# InputFilter.net
KiCad netlist of a schematic drawn in Altium Designer
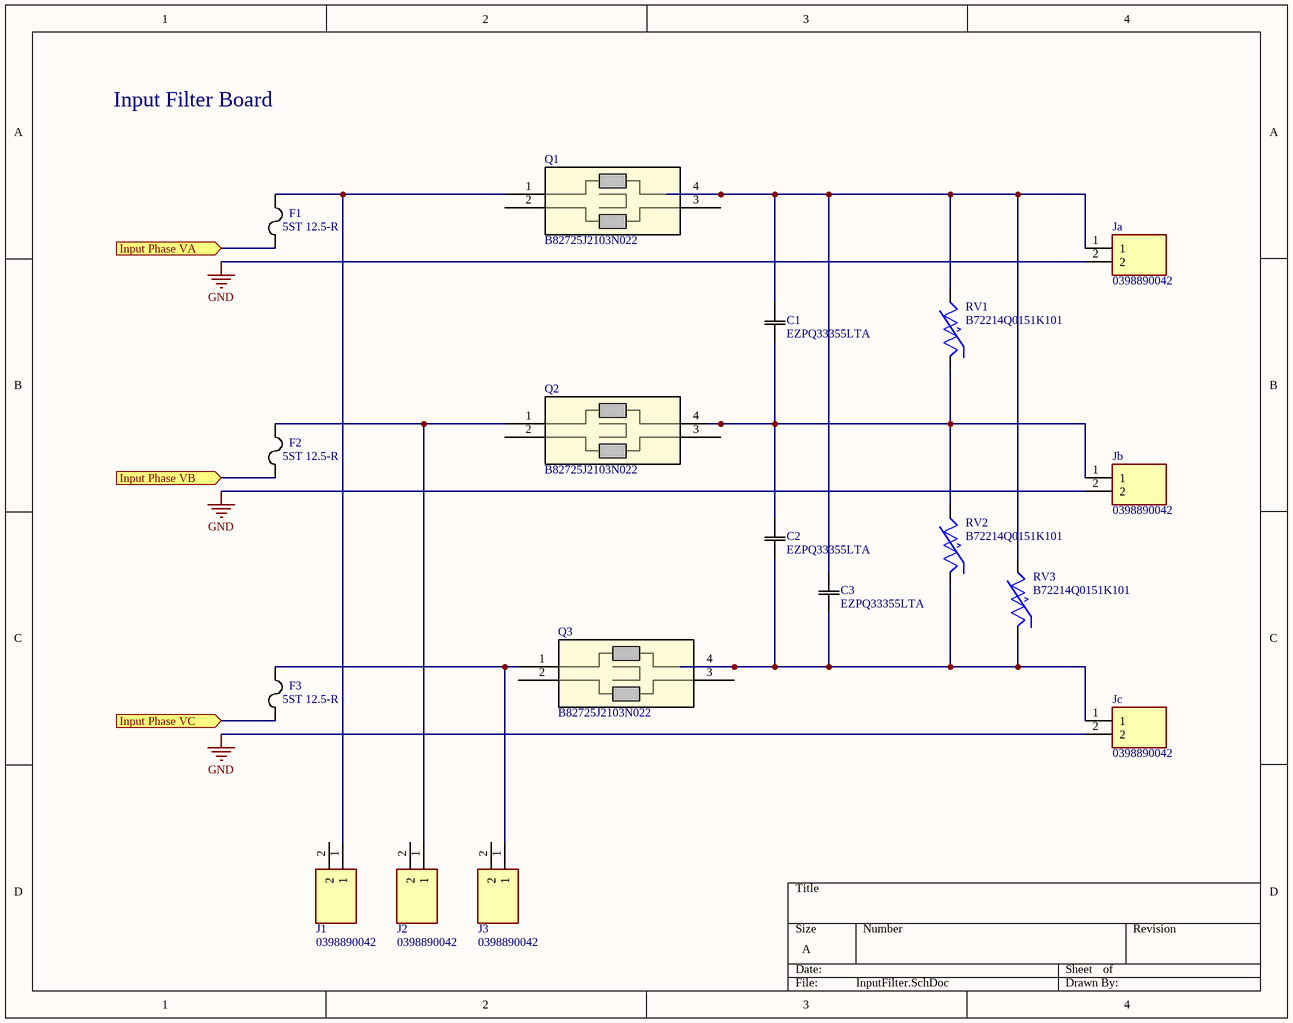
[diagram p0: InputFilter.SchDoc]

(export (version "E")
  (design (tool "Eeschema 10.0.6"))
  (components
    (comp (ref "C1")
      (value "EZPQ33355LTA")
      (footprint "CAP_EZPQ33_41p5X17-37p5_PAN")
      (description "No Description Available")
      (libsource (lib "EZPQ33355LTA") (part "EZPQ33355LTA"))
    )
    (comp (ref "C2")
      (value "EZPQ33355LTA")
      (footprint "CAP_EZPQ33_41p5X17-37p5_PAN")
      (description "No Description Available")
      (libsource (lib "EZPQ33355LTA") (part "EZPQ33355LTA"))
    )
    (comp (ref "C3")
      (value "EZPQ33355LTA")
      (footprint "CAP_EZPQ33_41p5X17-37p5_PAN")
      (description "No Description Available")
      (libsource (lib "EZPQ33355LTA") (part "EZPQ33355LTA"))
    )
    (comp (ref "F1")
      (value "5ST 12.5-R")
      (footprint "5S_MELF_BEL")
      (description "No Description Available")
      (libsource (lib "5ST12P5-R") (part "5ST 12.5-R"))
    )
    (comp (ref "F2")
      (value "5ST 12.5-R")
      (footprint "5S_MELF_BEL")
      (description "No Description Available")
      (libsource (lib "5ST12P5-R") (part "5ST 12.5-R"))
    )
    (comp (ref "F3")
      (value "5ST 12.5-R")
      (footprint "5S_MELF_BEL")
      (description "No Description Available")
      (libsource (lib "5ST12P5-R") (part "5ST 12.5-R"))
    )
    (comp (ref "J1")
      (value "0398890042")
      (footprint "0398890042")
      (description "Conn Eurostyle Block 2 POS 5.08mm Solder ST Thru-Hole 17.5A/Contact")
      (libsource (lib "") (part "0398890042_1"))
    )
    (comp (ref "J2")
      (value "0398890042")
      (footprint "0398890042")
      (description "Conn Eurostyle Block 2 POS 5.08mm Solder ST Thru-Hole 17.5A/Contact")
      (libsource (lib "") (part "0398890042_1"))
    )
    (comp (ref "J3")
      (value "0398890042")
      (footprint "0398890042")
      (description "Conn Eurostyle Block 2 POS 5.08mm Solder ST Thru-Hole 17.5A/Contact")
      (libsource (lib "") (part "0398890042_1"))
    )
    (comp (ref "Ja")
      (value "0398890042")
      (footprint "0398890042")
      (description "Conn Eurostyle Block 2 POS 5.08mm Solder ST Thru-Hole 17.5A/Contact")
      (libsource (lib "0398890042") (part "0398890042"))
    )
    (comp (ref "Jb")
      (value "0398890042")
      (footprint "0398890042")
      (description "Conn Eurostyle Block 2 POS 5.08mm Solder ST Thru-Hole 17.5A/Contact")
      (libsource (lib "0398890042") (part "0398890042"))
    )
    (comp (ref "Jc")
      (value "0398890042")
      (footprint "0398890042")
      (description "Conn Eurostyle Block 2 POS 5.08mm Solder ST Thru-Hole 17.5A/Contact")
      (libsource (lib "0398890042") (part "0398890042"))
    )
    (comp (ref "Q1")
      (value "B82725J2103N022")
      (footprint "B82725J2103N022_TDK")
      (description "No Description Available")
      (libsource (lib "B82725J2103N022") (part "B82725J2103N022"))
    )
    (comp (ref "Q2")
      (value "B82725J2103N022")
      (footprint "B82725J2103N022_TDK")
      (description "No Description Available")
      (libsource (lib "B82725J2103N022") (part "B82725J2103N022"))
    )
    (comp (ref "Q3")
      (value "B82725J2103N022")
      (footprint "B82725J2103N022_TDK")
      (description "No Description Available")
      (libsource (lib "B82725J2103N022") (part "B82725J2103N022"))
    )
    (comp (ref "RV1")
      (value "B72214Q0151K101")
      (footprint "VAR_B72214Q0151K101")
      (description "240 V 8 kA Varistor 1 Circuit Through Hole Radial")
      (fields (field (name "MF") "EPCOS"))
      (libsource (lib "B72214Q0151K101") (part "B72214Q0151K101"))
    )
    (comp (ref "RV2")
      (value "B72214Q0151K101")
      (footprint "VAR_B72214Q0151K101")
      (description "240 V 8 kA Varistor 1 Circuit Through Hole Radial")
      (fields (field (name "MF") "EPCOS"))
      (libsource (lib "B72214Q0151K101") (part "B72214Q0151K101"))
    )
    (comp (ref "RV3")
      (value "B72214Q0151K101")
      (footprint "VAR_B72214Q0151K101")
      (description "240 V 8 kA Varistor 1 Circuit Through Hole Radial")
      (fields (field (name "MF") "EPCOS"))
      (libsource (lib "B72214Q0151K101") (part "B72214Q0151K101"))
    )
  )
  (nets
    (net (code "1") (name "/Input Phase VA") (class "Default")
      (node (ref "F1") (pin "1") (pinfunction "1_1") (pintype "passive"))
    )
    (net (code "2") (name "/Input Phase VB") (class "Default")
      (node (ref "F2") (pin "1") (pinfunction "1_1") (pintype "passive"))
    )
    (net (code "3") (name "/Input Phase VC") (class "Default")
      (node (ref "F3") (pin "1") (pinfunction "1_1") (pintype "passive"))
    )
    (net (code "4") (name "GND") (class "Default")
      (node (ref "Ja") (pin "2") (pinfunction "2_2") (pintype "passive"))
      (node (ref "Jb") (pin "2") (pinfunction "2_2") (pintype "passive"))
      (node (ref "Jc") (pin "2") (pinfunction "2_2") (pintype "passive"))
    )
    (net (code "5") (name "Net-(C1-Pad1)") (class "Default")
      (node (ref "C1") (pin "1") (pinfunction "1_1") (pintype "passive"))
      (node (ref "C2") (pin "2") (pinfunction "2_2") (pintype "passive"))
      (node (ref "Jb") (pin "1") (pinfunction "1_1") (pintype "passive"))
      (node (ref "Q2") (pin "4") (pinfunction "4_4") (pintype "passive"))
      (node (ref "RV1") (pin "1") (pinfunction "1_1") (pintype "passive"))
      (node (ref "RV2") (pin "2") (pinfunction "2_2") (pintype "passive"))
    )
    (net (code "6") (name "Net-(C1-Pad2)") (class "Default")
      (node (ref "C1") (pin "2") (pinfunction "2_2") (pintype "passive"))
      (node (ref "C3") (pin "2") (pinfunction "2_2") (pintype "passive"))
      (node (ref "Ja") (pin "1") (pinfunction "1_1") (pintype "passive"))
      (node (ref "Q1") (pin "4") (pinfunction "4_4") (pintype "passive"))
      (node (ref "RV1") (pin "2") (pinfunction "2_2") (pintype "passive"))
      (node (ref "RV3") (pin "2") (pinfunction "2_2") (pintype "passive"))
    )
    (net (code "7") (name "Net-(C2-Pad1)") (class "Default")
      (node (ref "C2") (pin "1") (pinfunction "1_1") (pintype "passive"))
      (node (ref "C3") (pin "1") (pinfunction "1_1") (pintype "passive"))
      (node (ref "Jc") (pin "1") (pinfunction "1_1") (pintype "passive"))
      (node (ref "Q3") (pin "4") (pinfunction "4_4") (pintype "passive"))
      (node (ref "RV2") (pin "1") (pinfunction "1_1") (pintype "passive"))
      (node (ref "RV3") (pin "1") (pinfunction "1_1") (pintype "passive"))
    )
    (net (code "8") (name "Net-(F1-Pad2)") (class "Default")
      (node (ref "F1") (pin "2") (pinfunction "2_2") (pintype "passive"))
      (node (ref "J1") (pin "1") (pinfunction "1_1") (pintype "passive"))
      (node (ref "Q1") (pin "1") (pinfunction "1_1") (pintype "passive"))
    )
    (net (code "9") (name "Net-(F2-Pad2)") (class "Default")
      (node (ref "F2") (pin "2") (pinfunction "2_2") (pintype "passive"))
      (node (ref "J2") (pin "1") (pinfunction "1_1") (pintype "passive"))
      (node (ref "Q2") (pin "1") (pinfunction "1_1") (pintype "passive"))
    )
    (net (code "10") (name "Net-(F3-Pad2)") (class "Default")
      (node (ref "F3") (pin "2") (pinfunction "2_2") (pintype "passive"))
      (node (ref "J3") (pin "1") (pinfunction "1_1") (pintype "passive"))
      (node (ref "Q3") (pin "1") (pinfunction "1_1") (pintype "passive"))
    )
    (net (code "11") (name "unconnected-(J1-Pad2)") (class "Default")
      (node (ref "J1") (pin "2") (pinfunction "2_2") (pintype "passive"))
    )
    (net (code "12") (name "unconnected-(J2-Pad2)") (class "Default")
      (node (ref "J2") (pin "2") (pinfunction "2_2") (pintype "passive"))
    )
    (net (code "13") (name "unconnected-(J3-Pad2)") (class "Default")
      (node (ref "J3") (pin "2") (pinfunction "2_2") (pintype "passive"))
    )
    (net (code "14") (name "unconnected-(Q1-Pad2)") (class "Default")
      (node (ref "Q1") (pin "2") (pinfunction "2_2") (pintype "passive"))
    )
    (net (code "15") (name "unconnected-(Q1-Pad3)") (class "Default")
      (node (ref "Q1") (pin "3") (pinfunction "3_3") (pintype "passive"))
    )
    (net (code "16") (name "unconnected-(Q2-Pad2)") (class "Default")
      (node (ref "Q2") (pin "2") (pinfunction "2_2") (pintype "passive"))
    )
    (net (code "17") (name "unconnected-(Q2-Pad3)") (class "Default")
      (node (ref "Q2") (pin "3") (pinfunction "3_3") (pintype "passive"))
    )
    (net (code "18") (name "unconnected-(Q3-Pad2)") (class "Default")
      (node (ref "Q3") (pin "2") (pinfunction "2_2") (pintype "passive"))
    )
    (net (code "19") (name "unconnected-(Q3-Pad3)") (class "Default")
      (node (ref "Q3") (pin "3") (pinfunction "3_3") (pintype "passive"))
    )
  )
)
